# mainboard_rs485_v1_4.net
KiCad netlist of a schematic drawn in Altium Designer
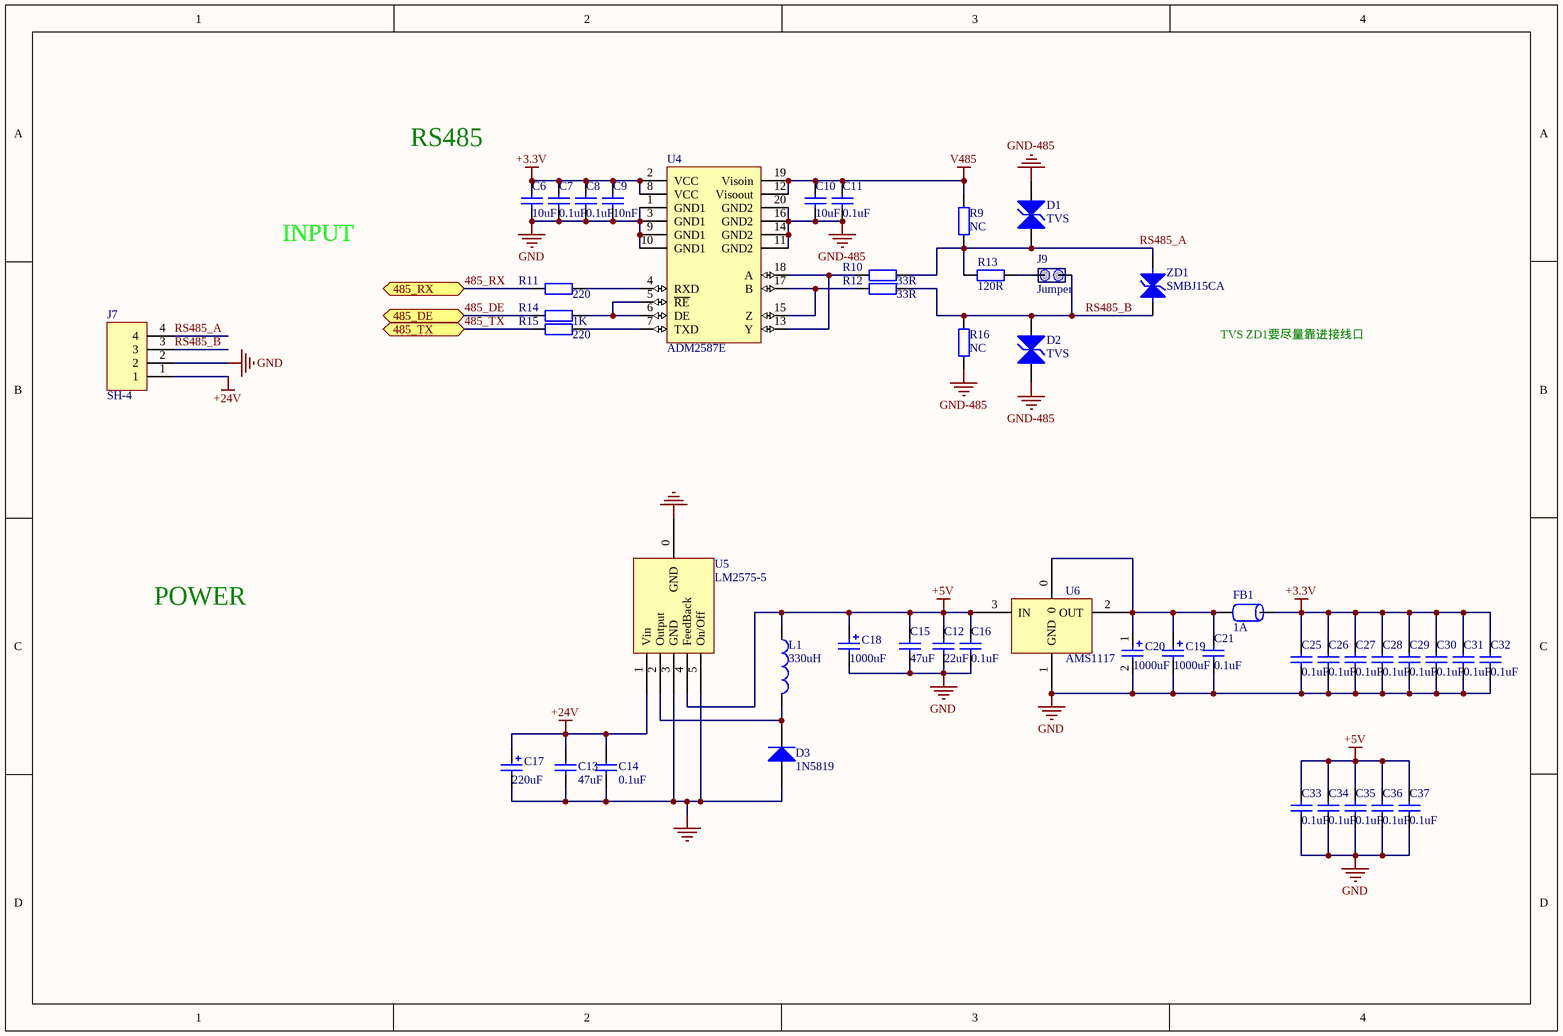
[diagram p0: mainboard_rs485.v1.4.SchDoc]

(export (version "E")
  (design (tool "Eeschema 10.0.6"))
  (components
    (comp (ref "C6")
      (value "10uF")
      (footprint "0805")
      (description "Capacitor")
      (fields (field (name "PUBLISHER") "Altium Limited"))
      (libsource (lib "TIAN's Schlib") (part "Cap"))
    )
    (comp (ref "C7")
      (value "0.1uF")
      (footprint "0805")
      (description "Capacitor")
      (fields (field (name "PUBLISHER") "Altium Limited"))
      (libsource (lib "TIAN's Schlib") (part "Cap"))
    )
    (comp (ref "C8")
      (value "0.1uF")
      (footprint "0805")
      (description "Capacitor")
      (fields (field (name "PUBLISHER") "Altium Limited"))
      (libsource (lib "TIAN's Schlib") (part "Cap"))
    )
    (comp (ref "C9")
      (value "10nF")
      (footprint "0805")
      (description "Capacitor")
      (fields (field (name "PUBLISHER") "Altium Limited"))
      (libsource (lib "TIAN's Schlib") (part "Cap"))
    )
    (comp (ref "C10")
      (value "10uF")
      (footprint "0805")
      (description "Capacitor")
      (fields (field (name "PUBLISHER") "Altium Limited"))
      (libsource (lib "TIAN's Schlib") (part "Cap"))
    )
    (comp (ref "C11")
      (value "0.1uF")
      (footprint "0805")
      (description "Capacitor")
      (fields (field (name "PUBLISHER") "Altium Limited"))
      (libsource (lib "TIAN's Schlib") (part "Cap"))
    )
    (comp (ref "C12") (value "22uF") (footprint "1206") (libsource (lib "Componet") (part "Cap0805")))
    (comp (ref "C13")
      (value "47uF")
      (footprint "1812")
      (description "Capacitor")
      (fields (field (name "PUBLISHER") "Altium Limited"))
      (libsource (lib "Miscellaneous Devices") (part "Cap"))
    )
    (comp (ref "C14")
      (value "0.1uF")
      (footprint "0805")
      (description "Capacitor")
      (fields (field (name "PUBLISHER") "Altium Limited"))
      (libsource (lib "Miscellaneous Devices") (part "Cap"))
    )
    (comp (ref "C15") (value "47uF") (footprint "1812") (libsource (lib "Componet") (part "Cap0805")))
    (comp (ref "C16") (value "0.1uF") (footprint "0805") (libsource (lib "Componet") (part "Cap0805")))
    (comp (ref "C17")
      (value "220uF")
      (footprint "CAP-5mm")
      (description "Polarized Capacitor (Radial)")
      (fields (field (name "PUBLISHER") "Altium Limited"))
      (libsource (lib "Miscellaneous Devices") (part "Cap Pol1"))
    )
    (comp (ref "C18")
      (value "1000uF")
      (footprint "CAP_SMT_10X10")
      (description "Polarized Capacitor (Radial)")
      (fields (field (name "PUBLISHER") "Altium Limited"))
      (libsource (lib "Miscellaneous Devices") (part "Cap Pol1"))
    )
    (comp (ref "C19")
      (value "1000uF")
      (footprint "CAP_SMT_10X10")
      (description "Polarized Capacitor (Radial)")
      (fields (field (name "PUBLISHER") "Altium Limited"))
      (libsource (lib "Miscellaneous Devices") (part "Cap Pol1"))
    )
    (comp (ref "C20")
      (value "1000uF")
      (footprint "CAP_SMT_10X10")
      (description "Polarized Capacitor (Radial)")
      (fields (field (name "PUBLISHER") "Altium Limited"))
      (libsource (lib "") (part "Cap Pol1_1"))
    )
    (comp (ref "C21") (value "0.1uF") (footprint "0805") (libsource (lib "Componet") (part "Cap0805")))
    (comp (ref "C25") (value "0.1uF") (footprint "0805") (libsource (lib "Componet") (part "Cap0805")))
    (comp (ref "C26") (value "0.1uF") (footprint "0805") (libsource (lib "Componet") (part "Cap0805")))
    (comp (ref "C27") (value "0.1uF") (footprint "0805") (libsource (lib "Componet") (part "Cap0805")))
    (comp (ref "C28") (value "0.1uF") (footprint "0805") (libsource (lib "Componet") (part "Cap0805")))
    (comp (ref "C29") (value "0.1uF") (footprint "0805") (libsource (lib "Componet") (part "Cap0805")))
    (comp (ref "C30") (value "0.1uF") (footprint "0805") (libsource (lib "Componet") (part "Cap0805")))
    (comp (ref "C31") (value "0.1uF") (footprint "0805") (libsource (lib "Componet") (part "Cap0805")))
    (comp (ref "C32") (value "0.1uF") (footprint "0805") (libsource (lib "Componet") (part "Cap0805")))
    (comp (ref "C33") (value "0.1uF") (footprint "0805") (libsource (lib "Componet") (part "Cap0805")))
    (comp (ref "C34") (value "0.1uF") (footprint "0805") (libsource (lib "Componet") (part "Cap0805")))
    (comp (ref "C35") (value "0.1uF") (footprint "0805") (libsource (lib "Componet") (part "Cap0805")))
    (comp (ref "C36") (value "0.1uF") (footprint "0805") (libsource (lib "Componet") (part "Cap0805")))
    (comp (ref "C37") (value "0.1uF") (footprint "0805") (libsource (lib "Componet") (part "Cap0805")))
    (comp (ref "D1")
      (value "TVS")
      (footprint "SMBJ_DO-214")
      (fields (field (name "PUBLISHER") "Altium Limited"))
      (libsource (lib "TIAN's Schlib") (part "TVS"))
    )
    (comp (ref "D2")
      (value "TVS")
      (footprint "SMBJ_DO-214")
      (fields (field (name "PUBLISHER") "Altium Limited"))
      (libsource (lib "TIAN's Schlib") (part "TVS"))
    )
    (comp (ref "D3")
      (value "1N5819")
      (footprint "Diode_TP2")
      (description "High Conductance Fast Diode")
      (fields (field (name "PUBLISHER") "Altium Limited"))
      (libsource (lib "Miscellaneous Devices") (part "Diode 1N4148"))
    )
    (comp (ref "FB1") (value "1A") (footprint "0805") (libsource (lib "Connector") (part "FERRITE")))
    (comp (ref "J7") (value "SH-4") (footprint "PWR") (libsource (lib "Connector") (part "SH-4")))
    (comp (ref "J9") (value "Jumper") (footprint "J254-2") (libsource (lib "Connector") (part "Jumper")))
    (comp (ref "L1")
      (value "330uH")
      (footprint "Inductance")
      (description "Inductor")
      (fields (field (name "PUBLISHER") "Altium Limited"))
      (libsource (lib "Miscellaneous Devices") (part "Inductor"))
    )
    (comp (ref "R9")
      (value "NC")
      (footprint "0805")
      (description "Resistor")
      (fields (field (name "PUBLISHER") "Altium Limited"))
      (libsource (lib "") (part "Res2_1"))
    )
    (comp (ref "R10")
      (value "33R")
      (footprint "0805")
      (description "Resistor")
      (fields (field (name "PUBLISHER") "Altium Limited"))
      (libsource (lib "") (part "Res2_2"))
    )
    (comp (ref "R11")
      (value "220")
      (footprint "0805")
      (description "Resistor")
      (fields (field (name "PUBLISHER") "Altium Limited"))
      (libsource (lib "") (part "Res2_1"))
    )
    (comp (ref "R12")
      (value "33R")
      (footprint "0805")
      (description "Resistor")
      (fields (field (name "PUBLISHER") "Altium Limited"))
      (libsource (lib "") (part "Res2_2"))
    )
    (comp (ref "R13")
      (value "120R")
      (footprint "0805")
      (description "Resistor")
      (fields (field (name "PUBLISHER") "Altium Limited"))
      (libsource (lib "TIAN's Schlib") (part "Res2"))
    )
    (comp (ref "R14")
      (value "1K")
      (footprint "0805")
      (description "Resistor")
      (fields (field (name "PUBLISHER") "Altium Limited"))
      (libsource (lib "") (part "Res2_1"))
    )
    (comp (ref "R15")
      (value "220")
      (footprint "0805")
      (description "Resistor")
      (fields (field (name "PUBLISHER") "Altium Limited"))
      (libsource (lib "") (part "Res2_1"))
    )
    (comp (ref "R16")
      (value "NC")
      (footprint "0805")
      (description "Resistor")
      (fields (field (name "PUBLISHER") "Altium Limited"))
      (libsource (lib "") (part "Res2_1"))
    )
    (comp (ref "U4")
      (value "ADM2587E")
      (footprint "SOIC_W_20")
      (description "isolated DC-DC RS485")
      (libsource (lib "TIAN's Schlib") (part "ADM2587E"))
    )
    (comp (ref "U5") (value "LM2575-5") (footprint "TO-263") (libsource (lib "Leon") (part "LM25XX")))
    (comp (ref "U6") (value "AMS1117") (footprint "TO-223") (libsource (lib "Chip") (part "AMS1117")))
    (comp (ref "ZD1")
      (value "SMBJ15CA")
      (footprint "DO-214AA/SMB")
      (description "瞬态抑制二极管")
      (libsource (lib "ALARM") (part "TVS"))
    )
  )
  (nets
    (net (code "1") (name "+3.3V") (class "Default")
      (node (ref "C25") (pin "2") (pinfunction "2_2") (pintype "passive"))
      (node (ref "C26") (pin "2") (pinfunction "2_2") (pintype "passive"))
      (node (ref "C27") (pin "2") (pinfunction "2_2") (pintype "passive"))
      (node (ref "C28") (pin "2") (pinfunction "2_2") (pintype "passive"))
      (node (ref "C29") (pin "2") (pinfunction "2_2") (pintype "passive"))
      (node (ref "C30") (pin "2") (pinfunction "2_2") (pintype "passive"))
      (node (ref "C31") (pin "2") (pinfunction "2_2") (pintype "passive"))
      (node (ref "C32") (pin "2") (pinfunction "2_2") (pintype "passive"))
      (node (ref "C6") (pin "2") (pinfunction "2_2") (pintype "passive"))
      (node (ref "C7") (pin "2") (pinfunction "2_2") (pintype "passive"))
      (node (ref "C8") (pin "2") (pinfunction "2_2") (pintype "passive"))
      (node (ref "C9") (pin "2") (pinfunction "2_2") (pintype "passive"))
      (node (ref "FB1") (pin "2") (pinfunction "2_2") (pintype "passive"))
      (node (ref "U4") (pin "2") (pinfunction "VCC_2") (pintype "passive"))
      (node (ref "U4") (pin "8") (pinfunction "VCC_8") (pintype "passive"))
    )
    (net (code "2") (name "+5V") (class "Default")
      (node (ref "C12") (pin "2") (pinfunction "2_2") (pintype "passive"))
      (node (ref "C15") (pin "2") (pinfunction "2_2") (pintype "passive"))
      (node (ref "C16") (pin "2") (pinfunction "2_2") (pintype "passive"))
      (node (ref "C18") (pin "1") (pinfunction "1_1") (pintype "passive"))
      (node (ref "C33") (pin "2") (pinfunction "2_2") (pintype "passive"))
      (node (ref "C34") (pin "2") (pinfunction "2_2") (pintype "passive"))
      (node (ref "C35") (pin "2") (pinfunction "2_2") (pintype "passive"))
      (node (ref "C36") (pin "2") (pinfunction "2_2") (pintype "passive"))
      (node (ref "C37") (pin "2") (pinfunction "2_2") (pintype "passive"))
      (node (ref "L1") (pin "1") (pinfunction "1_1") (pintype "passive"))
      (node (ref "U5") (pin "4") (pinfunction "FeedBack_4") (pintype "passive"))
      (node (ref "U6") (pin "3") (pinfunction "IN_3") (pintype "passive"))
    )
    (net (code "3") (name "+24V") (class "Default")
      (node (ref "C13") (pin "2") (pinfunction "2_2") (pintype "passive"))
      (node (ref "C14") (pin "2") (pinfunction "2_2") (pintype "passive"))
      (node (ref "C17") (pin "1") (pinfunction "1_1") (pintype "passive"))
      (node (ref "J7") (pin "1") (pinfunction "1_1") (pintype "passive"))
      (node (ref "U5") (pin "1") (pinfunction "Vin_1") (pintype "passive"))
    )
    (net (code "4") (name "/485_DE") (class "Default")
      (node (ref "R14") (pin "1") (pinfunction "1_1") (pintype "passive"))
    )
    (net (code "5") (name "/485_RX") (class "Default")
      (node (ref "R11") (pin "1") (pinfunction "1_1") (pintype "passive"))
    )
    (net (code "6") (name "/485_TX") (class "Default")
      (node (ref "R15") (pin "1") (pinfunction "1_1") (pintype "passive"))
    )
    (net (code "7") (name "/RS485_A") (class "Default")
      (node (ref "D1") (pin "2") (pinfunction "K_2") (pintype "passive"))
      (node (ref "J7") (pin "4") (pinfunction "4_4") (pintype "passive"))
      (node (ref "R10") (pin "2") (pinfunction "2_2") (pintype "passive"))
      (node (ref "R13") (pin "2") (pinfunction "2_2") (pintype "passive"))
      (node (ref "R9") (pin "1") (pinfunction "1_1") (pintype "passive"))
      (node (ref "ZD1") (pin "1") (pinfunction "1_1") (pintype "passive"))
    )
    (net (code "8") (name "/RS485_B") (class "Default")
      (node (ref "D2") (pin "2") (pinfunction "K_2") (pintype "passive"))
      (node (ref "J7") (pin "3") (pinfunction "3_3") (pintype "passive"))
      (node (ref "J9") (pin "1") (pinfunction "1_1") (pintype "passive"))
      (node (ref "R12") (pin "2") (pinfunction "2_2") (pintype "passive"))
      (node (ref "R16") (pin "2") (pinfunction "2_2") (pintype "passive"))
      (node (ref "ZD1") (pin "2") (pinfunction "2_2") (pintype "passive"))
    )
    (net (code "9") (name "GND") (class "Default")
      (node (ref "C12") (pin "1") (pinfunction "1_1") (pintype "passive"))
      (node (ref "C13") (pin "1") (pinfunction "1_1") (pintype "passive"))
      (node (ref "C14") (pin "1") (pinfunction "1_1") (pintype "passive"))
      (node (ref "C15") (pin "1") (pinfunction "1_1") (pintype "passive"))
      (node (ref "C16") (pin "1") (pinfunction "1_1") (pintype "passive"))
      (node (ref "C17") (pin "2") (pinfunction "2_2") (pintype "passive"))
      (node (ref "C18") (pin "2") (pinfunction "2_2") (pintype "passive"))
      (node (ref "C19") (pin "2") (pinfunction "2_2") (pintype "passive"))
      (node (ref "C20") (pin "2") (pinfunction "2_2") (pintype "passive"))
      (node (ref "C21") (pin "1") (pinfunction "1_1") (pintype "passive"))
      (node (ref "C25") (pin "1") (pinfunction "1_1") (pintype "passive"))
      (node (ref "C26") (pin "1") (pinfunction "1_1") (pintype "passive"))
      (node (ref "C27") (pin "1") (pinfunction "1_1") (pintype "passive"))
      (node (ref "C28") (pin "1") (pinfunction "1_1") (pintype "passive"))
      (node (ref "C29") (pin "1") (pinfunction "1_1") (pintype "passive"))
      (node (ref "C30") (pin "1") (pinfunction "1_1") (pintype "passive"))
      (node (ref "C31") (pin "1") (pinfunction "1_1") (pintype "passive"))
      (node (ref "C32") (pin "1") (pinfunction "1_1") (pintype "passive"))
      (node (ref "C33") (pin "1") (pinfunction "1_1") (pintype "passive"))
      (node (ref "C34") (pin "1") (pinfunction "1_1") (pintype "passive"))
      (node (ref "C35") (pin "1") (pinfunction "1_1") (pintype "passive"))
      (node (ref "C36") (pin "1") (pinfunction "1_1") (pintype "passive"))
      (node (ref "C37") (pin "1") (pinfunction "1_1") (pintype "passive"))
      (node (ref "C6") (pin "1") (pinfunction "1_1") (pintype "passive"))
      (node (ref "C7") (pin "1") (pinfunction "1_1") (pintype "passive"))
      (node (ref "C8") (pin "1") (pinfunction "1_1") (pintype "passive"))
      (node (ref "C9") (pin "1") (pinfunction "1_1") (pintype "passive"))
      (node (ref "D3") (pin "1") (pinfunction "A_1") (pintype "passive"))
      (node (ref "J7") (pin "2") (pinfunction "2_2") (pintype "passive"))
      (node (ref "U4") (pin "1") (pinfunction "GND1_1") (pintype "passive"))
      (node (ref "U4") (pin "10") (pinfunction "GND1_10") (pintype "passive"))
      (node (ref "U4") (pin "3") (pinfunction "GND1_3") (pintype "passive"))
      (node (ref "U4") (pin "9") (pinfunction "GND1_9") (pintype "passive"))
      (node (ref "U5") (pin "0") (pinfunction "GND_0") (pintype "passive"))
      (node (ref "U5") (pin "3") (pinfunction "GND_3") (pintype "passive"))
      (node (ref "U5") (pin "5") (pinfunction "On/Off_5") (pintype "passive"))
      (node (ref "U6") (pin "1") (pinfunction "GND_1") (pintype "passive"))
    )
    (net (code "10") (name "GND-485") (class "Default")
      (node (ref "C10") (pin "1") (pinfunction "1_1") (pintype "passive"))
      (node (ref "C11") (pin "1") (pinfunction "1_1") (pintype "passive"))
      (node (ref "D1") (pin "1") (pinfunction "A_1") (pintype "passive"))
      (node (ref "D2") (pin "1") (pinfunction "A_1") (pintype "passive"))
      (node (ref "R16") (pin "1") (pinfunction "1_1") (pintype "passive"))
      (node (ref "U4") (pin "11") (pinfunction "GND2_11") (pintype "passive"))
      (node (ref "U4") (pin "14") (pinfunction "GND2_14") (pintype "passive"))
      (node (ref "U4") (pin "16") (pinfunction "GND2_16") (pintype "passive"))
      (node (ref "U4") (pin "20") (pinfunction "GND2_20") (pintype "passive"))
    )
    (net (code "11") (name "Net-(D3-K)") (class "Default")
      (node (ref "D3") (pin "2") (pinfunction "K_2") (pintype "passive"))
      (node (ref "L1") (pin "2") (pinfunction "2_2") (pintype "passive"))
      (node (ref "U5") (pin "2") (pinfunction "Output_2") (pintype "passive"))
    )
    (net (code "12") (name "Net-(J9-Pad2)") (class "Default")
      (node (ref "J9") (pin "2") (pinfunction "2_2") (pintype "passive"))
      (node (ref "R13") (pin "1") (pinfunction "1_1") (pintype "passive"))
    )
    (net (code "13") (name "Net-(U4-A)") (class "Default")
      (node (ref "R10") (pin "1") (pinfunction "1_1") (pintype "passive"))
      (node (ref "U4") (pin "13") (pinfunction "Y_13") (pintype "bidirectional"))
      (node (ref "U4") (pin "18") (pinfunction "A_18") (pintype "bidirectional"))
    )
    (net (code "14") (name "Net-(U4-B)") (class "Default")
      (node (ref "R12") (pin "1") (pinfunction "1_1") (pintype "passive"))
      (node (ref "U4") (pin "15") (pinfunction "Z_15") (pintype "bidirectional"))
      (node (ref "U4") (pin "17") (pinfunction "B_17") (pintype "bidirectional"))
    )
    (net (code "15") (name "Net-(U4-DE)") (class "Default")
      (node (ref "R14") (pin "2") (pinfunction "2_2") (pintype "passive"))
      (node (ref "U4") (pin "5") (pinfunction "~{RE}_5") (pintype "bidirectional"))
      (node (ref "U4") (pin "6") (pinfunction "DE_6") (pintype "bidirectional"))
    )
    (net (code "16") (name "Net-(U4-RXD)") (class "Default")
      (node (ref "R11") (pin "2") (pinfunction "2_2") (pintype "passive"))
      (node (ref "U4") (pin "4") (pinfunction "RXD_4") (pintype "bidirectional"))
    )
    (net (code "17") (name "Net-(U4-TXD)") (class "Default")
      (node (ref "R15") (pin "2") (pinfunction "2_2") (pintype "passive"))
      (node (ref "U4") (pin "7") (pinfunction "TXD_7") (pintype "bidirectional"))
    )
    (net (code "18") (name "Net-(U6-OUT)") (class "Default")
      (node (ref "C19") (pin "1") (pinfunction "1_1") (pintype "passive"))
      (node (ref "C20") (pin "1") (pinfunction "1_1") (pintype "passive"))
      (node (ref "C21") (pin "2") (pinfunction "2_2") (pintype "passive"))
      (node (ref "FB1") (pin "1") (pinfunction "1_1") (pintype "passive"))
      (node (ref "U6") (pin "0") (pinfunction "0_0") (pintype "passive"))
      (node (ref "U6") (pin "2") (pinfunction "OUT_2") (pintype "passive"))
    )
    (net (code "19") (name "V485") (class "Default")
      (node (ref "C10") (pin "2") (pinfunction "2_2") (pintype "passive"))
      (node (ref "C11") (pin "2") (pinfunction "2_2") (pintype "passive"))
      (node (ref "R9") (pin "2") (pinfunction "2_2") (pintype "passive"))
      (node (ref "U4") (pin "12") (pinfunction "Visoout_12") (pintype "passive"))
      (node (ref "U4") (pin "19") (pinfunction "Visoin_19") (pintype "passive"))
    )
  )
)
